# Connectors.net
KiCad netlist of a schematic drawn in Altium Designer
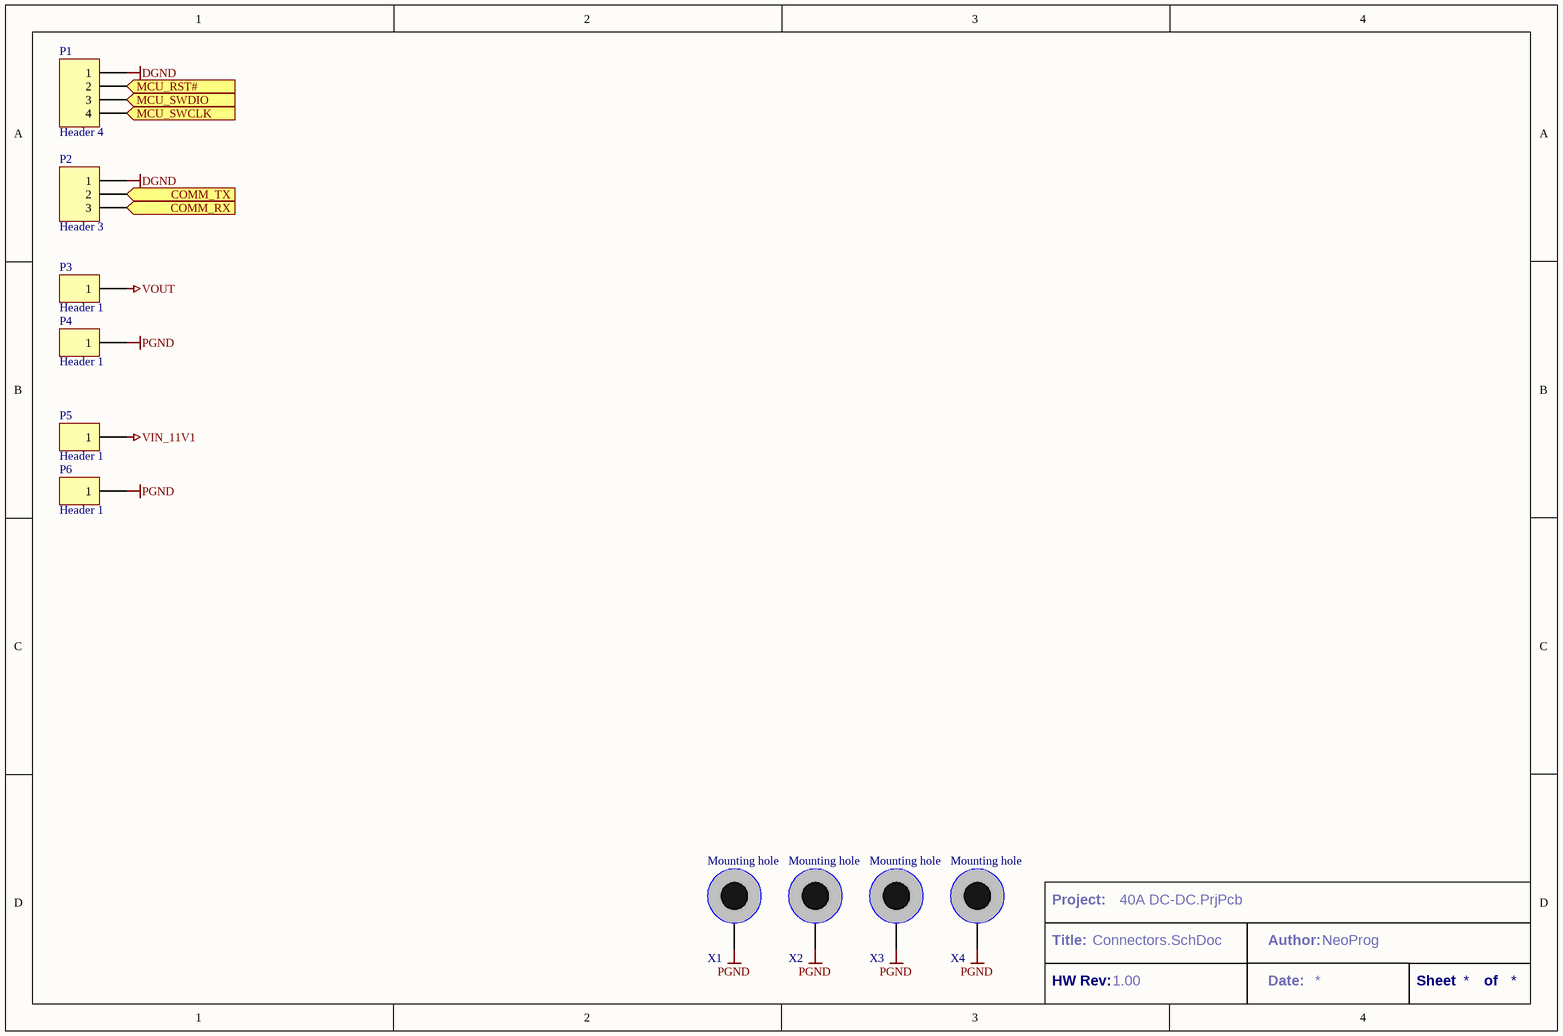
[diagram p0: Connectors.SchDoc]

(export (version "E")
  (design (tool "Eeschema 10.0.6"))
  (components
    (comp (ref "P1")
      (value "Header 4")
      (footprint "HDR_SMD_1X4_1.50")
      (description "Header, 4-Pin")
      (fields (field (name "PUBLISHER") "Altium Limited"))
      (libsource (lib "connectors") (part "Header 4"))
    )
    (comp (ref "P2")
      (value "Header 3")
      (footprint "HDR_SMD_1X3_1.50")
      (description "Header, 3-Pin")
      (fields (field (name "PUBLISHER") "Altium Limited"))
      (libsource (lib "connectors") (part "Header 3"))
    )
    (comp (ref "P3")
      (value "Header 1")
      (footprint "WIRE_SMD_5X5")
      (description "Header, 1-Pin")
      (fields (field (name "PUBLISHER") "Altium Limited"))
      (libsource (lib "connectors") (part "Header 1"))
    )
    (comp (ref "P4")
      (value "Header 1")
      (footprint "WIRE_SMD_5X5")
      (description "Header, 1-Pin")
      (fields (field (name "PUBLISHER") "Altium Limited"))
      (libsource (lib "connectors") (part "Header 1"))
    )
    (comp (ref "P5")
      (value "Header 1")
      (footprint "WIRE_SMD_5X5")
      (description "Header, 1-Pin")
      (fields (field (name "PUBLISHER") "Altium Limited"))
      (libsource (lib "connectors") (part "Header 1"))
    )
    (comp (ref "P6")
      (value "Header 1")
      (footprint "WIRE_SMD_5X5")
      (description "Header, 1-Pin")
      (fields (field (name "PUBLISHER") "Altium Limited"))
      (libsource (lib "connectors") (part "Header 1"))
    )
    (comp (ref "X1")
      (value "Mounting hole")
      (footprint "HOLE_M3_D6.0/3.5")
      (description "Hole for screw M3, outline D6")
      (libsource (lib "connectors") (part "Mounting hole"))
    )
    (comp (ref "X2")
      (value "Mounting hole")
      (footprint "HOLE_M3_D6.0/3.5")
      (description "Hole for screw M3, outline D6")
      (libsource (lib "connectors") (part "Mounting hole"))
    )
    (comp (ref "X3")
      (value "Mounting hole")
      (footprint "HOLE_M3_D6.0/3.5")
      (description "Hole for screw M3, outline D6")
      (libsource (lib "connectors") (part "Mounting hole"))
    )
    (comp (ref "X4")
      (value "Mounting hole")
      (footprint "HOLE_M3_D6.0/3.5")
      (description "Hole for screw M3, outline D6")
      (libsource (lib "connectors") (part "Mounting hole"))
    )
  )
  (nets
    (net (code "1") (name "/COMM_RX") (class "Default")
      (node (ref "P2") (pin "3") (pinfunction "3_3") (pintype "passive"))
    )
    (net (code "2") (name "/COMM_TX") (class "Default")
      (node (ref "P2") (pin "2") (pinfunction "2_2") (pintype "passive"))
    )
    (net (code "3") (name "/MCU_RST#") (class "Default")
      (node (ref "P1") (pin "2") (pinfunction "2_2") (pintype "passive"))
    )
    (net (code "4") (name "/MCU_SWCLK") (class "Default")
      (node (ref "P1") (pin "4") (pinfunction "4_4") (pintype "passive"))
    )
    (net (code "5") (name "/MCU_SWDIO") (class "Default")
      (node (ref "P1") (pin "3") (pinfunction "3_3") (pintype "passive"))
    )
    (net (code "6") (name "DGND") (class "Default")
      (node (ref "P1") (pin "1") (pinfunction "1_1") (pintype "passive"))
      (node (ref "P2") (pin "1") (pinfunction "1_1") (pintype "passive"))
    )
    (net (code "7") (name "PGND") (class "Default")
      (node (ref "P4") (pin "1") (pinfunction "1_1") (pintype "passive"))
      (node (ref "P6") (pin "1") (pinfunction "1_1") (pintype "passive"))
      (node (ref "X1") (pin "1") (pintype "passive"))
      (node (ref "X2") (pin "1") (pintype "passive"))
      (node (ref "X3") (pin "1") (pintype "passive"))
      (node (ref "X4") (pin "1") (pintype "passive"))
    )
    (net (code "8") (name "VIN_11V1") (class "Default")
      (node (ref "P5") (pin "1") (pinfunction "1_1") (pintype "passive"))
    )
    (net (code "9") (name "VOUT") (class "Default")
      (node (ref "P3") (pin "1") (pinfunction "1_1") (pintype "passive"))
    )
  )
)
